# BB-ADC.net
KiCad netlist of a schematic drawn in Altium Designer
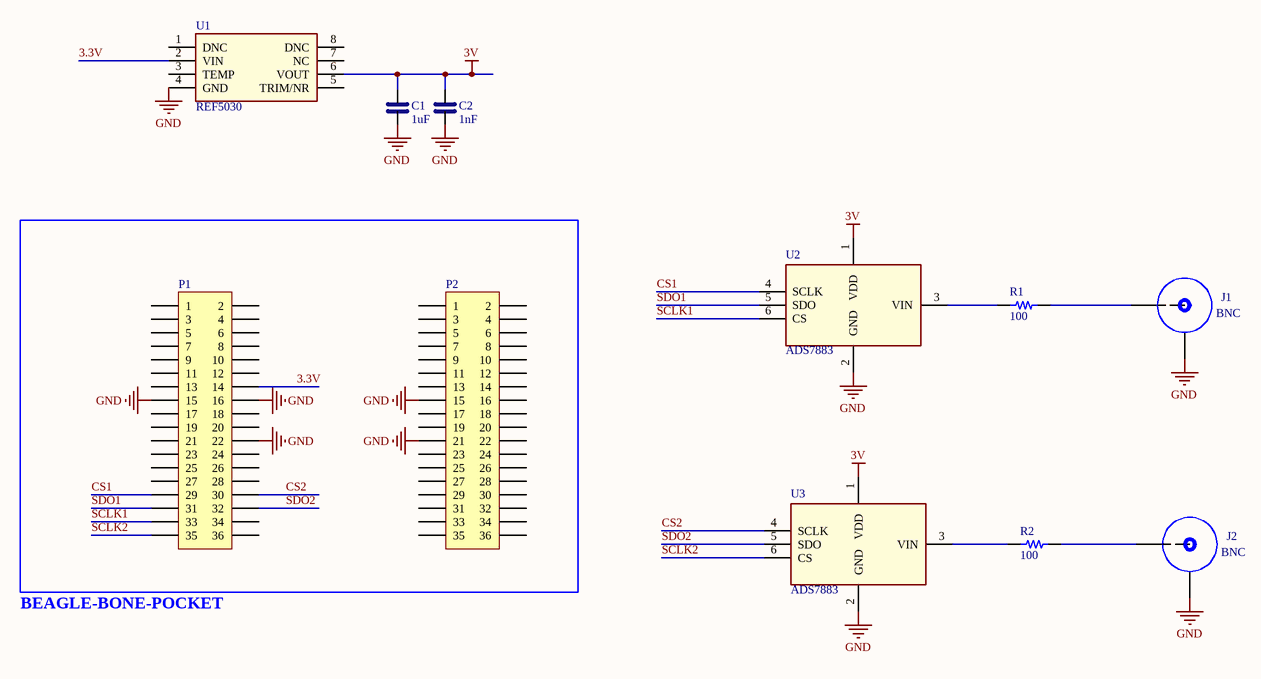
[diagram p0: BB-ADC.SchDoc]

(export (version "E")
  (design (tool "Eeschema 10.0.6"))
  (components
    (comp (ref "C1")
      (value "1uF")
      (footprint "CAP 0805/2012")
      (libsource (lib "Capacitors") (part "CAP 0805/2012"))
    )
    (comp (ref "C2")
      (value "1nF")
      (footprint "CAP 0805/2012")
      (libsource (lib "Capacitors") (part "CAP 0805/2012"))
    )
    (comp (ref "J1")
      (value "BNC")
      (footprint "BNC Straight")
      (description "RF Connectors / Coaxial Connectors BNC")
      (libsource (lib "Connectors") (part "BNC"))
    )
    (comp (ref "J2")
      (value "BNC")
      (footprint "BNC Straight")
      (description "RF Connectors / Coaxial Connectors BNC")
      (libsource (lib "Connectors") (part "BNC"))
    )
    (comp (ref "P1")
      (value "Beagle-Pocket")
      (footprint "HDR2X18")
      (description "Header, 18-Pin, Dual row")
      (fields (field (name "PUBLISHER") "Altium Limited"))
      (libsource (lib "Miscellaneous Connectors") (part "Header 18X2"))
    )
    (comp (ref "P2")
      (value "Beagle-Pocket")
      (footprint "HDR2X18")
      (description "Header, 18-Pin, Dual row")
      (fields (field (name "PUBLISHER") "Altium Limited"))
      (libsource (lib "Miscellaneous Connectors") (part "Header 18X2"))
    )
    (comp (ref "R1")
      (value "100")
      (footprint "RES 0805/2012")
      (libsource (lib "Resistors") (part "RES 0805/2012 ( 1/8W )"))
    )
    (comp (ref "R2")
      (value "100")
      (footprint "RES 0805/2012")
      (libsource (lib "Resistors") (part "RES 0805/2012 ( 1/8W )"))
    )
    (comp (ref "U1")
      (value "REF5030")
      (footprint "SOIC-8 (150mil-3.9mm width)")
      (description "Series Voltage Reference IC ±0.1% 10mA")
      (libsource (lib "Integrated Circuits") (part "REF5030"))
    )
    (comp (ref "U2")
      (value "ADS7883")
      (footprint "SOT-23-6")
      (description "12 Bit Analog to Digital Converter 1 Input 1 SAR SOT-23-6")
      (libsource (lib "Integrated Circuits") (part "ADS7883"))
    )
    (comp (ref "U3")
      (value "ADS7883")
      (footprint "SOT-23-6")
      (description "12 Bit Analog to Digital Converter 1 Input 1 SAR SOT-23-6")
      (libsource (lib "Integrated Circuits") (part "ADS7883"))
    )
  )
  (nets
    (net (code "1") (name "/3.3V") (class "Default")
      (node (ref "P1") (pin "14") (pinfunction "14_14") (pintype "passive"))
      (node (ref "U1") (pin "2") (pinfunction "VIN_2") (pintype "passive"))
    )
    (net (code "2") (name "/CS1") (class "Default")
      (node (ref "P1") (pin "29") (pinfunction "29_29") (pintype "passive"))
      (node (ref "U2") (pin "4") (pinfunction "SCLK_4") (pintype "passive"))
    )
    (net (code "3") (name "/CS2") (class "Default")
      (node (ref "P1") (pin "30") (pinfunction "30_30") (pintype "passive"))
      (node (ref "U3") (pin "4") (pinfunction "SCLK_4") (pintype "passive"))
    )
    (net (code "4") (name "/SCLK1") (class "Default")
      (node (ref "P1") (pin "33") (pinfunction "33_33") (pintype "passive"))
      (node (ref "U2") (pin "6") (pinfunction "CS_6") (pintype "passive"))
    )
    (net (code "5") (name "/SCLK2") (class "Default")
      (node (ref "P1") (pin "35") (pinfunction "35_35") (pintype "passive"))
      (node (ref "U3") (pin "6") (pinfunction "CS_6") (pintype "passive"))
    )
    (net (code "6") (name "/SDO1") (class "Default")
      (node (ref "P1") (pin "31") (pinfunction "31_31") (pintype "passive"))
      (node (ref "U2") (pin "5") (pinfunction "SDO_5") (pintype "passive"))
    )
    (net (code "7") (name "/SDO2") (class "Default")
      (node (ref "P1") (pin "32") (pinfunction "32_32") (pintype "passive"))
      (node (ref "U3") (pin "5") (pinfunction "SDO_5") (pintype "passive"))
    )
    (net (code "8") (name "3V") (class "Default")
      (node (ref "C1") (pin "2") (pinfunction "2_2") (pintype "passive"))
      (node (ref "C2") (pin "2") (pinfunction "2_2") (pintype "passive"))
      (node (ref "U1") (pin "6") (pinfunction "VOUT_6") (pintype "passive"))
      (node (ref "U2") (pin "1") (pinfunction "VDD_1") (pintype "passive"))
      (node (ref "U3") (pin "1") (pinfunction "VDD_1") (pintype "passive"))
    )
    (net (code "9") (name "GND") (class "Default")
      (node (ref "C1") (pin "1") (pinfunction "1_1") (pintype "passive"))
      (node (ref "C2") (pin "1") (pinfunction "1_1") (pintype "passive"))
      (node (ref "J1") (pin "2") (pinfunction "2_2") (pintype "passive"))
      (node (ref "J2") (pin "2") (pinfunction "2_2") (pintype "passive"))
      (node (ref "P1") (pin "15") (pinfunction "15_15") (pintype "passive"))
      (node (ref "P1") (pin "16") (pinfunction "16_16") (pintype "passive"))
      (node (ref "P1") (pin "22") (pinfunction "22_22") (pintype "passive"))
      (node (ref "P2") (pin "15") (pinfunction "15_15") (pintype "passive"))
      (node (ref "P2") (pin "21") (pinfunction "21_21") (pintype "passive"))
      (node (ref "U1") (pin "4") (pinfunction "GND_4") (pintype "passive"))
      (node (ref "U2") (pin "2") (pinfunction "GND_2") (pintype "passive"))
      (node (ref "U3") (pin "2") (pinfunction "GND_2") (pintype "passive"))
    )
    (net (code "10") (name "Net-(J1-Pad1)") (class "Default")
      (node (ref "J1") (pin "1") (pinfunction "1_1") (pintype "passive"))
      (node (ref "R1") (pin "2") (pinfunction "2_2") (pintype "passive"))
    )
    (net (code "11") (name "Net-(J2-Pad1)") (class "Default")
      (node (ref "J2") (pin "1") (pinfunction "1_1") (pintype "passive"))
      (node (ref "R2") (pin "2") (pinfunction "2_2") (pintype "passive"))
    )
    (net (code "12") (name "Net-(U2-VIN)") (class "Default")
      (node (ref "R1") (pin "1") (pinfunction "1_1") (pintype "passive"))
      (node (ref "U2") (pin "3") (pinfunction "VIN_3") (pintype "passive"))
    )
    (net (code "13") (name "Net-(U3-VIN)") (class "Default")
      (node (ref "R2") (pin "1") (pinfunction "1_1") (pintype "passive"))
      (node (ref "U3") (pin "3") (pinfunction "VIN_3") (pintype "passive"))
    )
    (net (code "14") (name "unconnected-(P1-Pad1)") (class "Default")
      (node (ref "P1") (pin "1") (pinfunction "1_1") (pintype "passive"))
    )
    (net (code "15") (name "unconnected-(P1-Pad2)") (class "Default")
      (node (ref "P1") (pin "2") (pinfunction "2_2") (pintype "passive"))
    )
    (net (code "16") (name "unconnected-(P1-Pad3)") (class "Default")
      (node (ref "P1") (pin "3") (pinfunction "3_3") (pintype "passive"))
    )
    (net (code "17") (name "unconnected-(P1-Pad4)") (class "Default")
      (node (ref "P1") (pin "4") (pinfunction "4_4") (pintype "passive"))
    )
    (net (code "18") (name "unconnected-(P1-Pad5)") (class "Default")
      (node (ref "P1") (pin "5") (pinfunction "5_5") (pintype "passive"))
    )
    (net (code "19") (name "unconnected-(P1-Pad6)") (class "Default")
      (node (ref "P1") (pin "6") (pinfunction "6_6") (pintype "passive"))
    )
    (net (code "20") (name "unconnected-(P1-Pad7)") (class "Default")
      (node (ref "P1") (pin "7") (pinfunction "7_7") (pintype "passive"))
    )
    (net (code "21") (name "unconnected-(P1-Pad8)") (class "Default")
      (node (ref "P1") (pin "8") (pinfunction "8_8") (pintype "passive"))
    )
    (net (code "22") (name "unconnected-(P1-Pad9)") (class "Default")
      (node (ref "P1") (pin "9") (pinfunction "9_9") (pintype "passive"))
    )
    (net (code "23") (name "unconnected-(P1-Pad10)") (class "Default")
      (node (ref "P1") (pin "10") (pinfunction "10_10") (pintype "passive"))
    )
    (net (code "24") (name "unconnected-(P1-Pad11)") (class "Default")
      (node (ref "P1") (pin "11") (pinfunction "11_11") (pintype "passive"))
    )
    (net (code "25") (name "unconnected-(P1-Pad12)") (class "Default")
      (node (ref "P1") (pin "12") (pinfunction "12_12") (pintype "passive"))
    )
    (net (code "26") (name "unconnected-(P1-Pad13)") (class "Default")
      (node (ref "P1") (pin "13") (pinfunction "13_13") (pintype "passive"))
    )
    (net (code "27") (name "unconnected-(P1-Pad17)") (class "Default")
      (node (ref "P1") (pin "17") (pinfunction "17_17") (pintype "passive"))
    )
    (net (code "28") (name "unconnected-(P1-Pad18)") (class "Default")
      (node (ref "P1") (pin "18") (pinfunction "18_18") (pintype "passive"))
    )
    (net (code "29") (name "unconnected-(P1-Pad19)") (class "Default")
      (node (ref "P1") (pin "19") (pinfunction "19_19") (pintype "passive"))
    )
    (net (code "30") (name "unconnected-(P1-Pad20)") (class "Default")
      (node (ref "P1") (pin "20") (pinfunction "20_20") (pintype "passive"))
    )
    (net (code "31") (name "unconnected-(P1-Pad21)") (class "Default")
      (node (ref "P1") (pin "21") (pinfunction "21_21") (pintype "passive"))
    )
    (net (code "32") (name "unconnected-(P1-Pad23)") (class "Default")
      (node (ref "P1") (pin "23") (pinfunction "23_23") (pintype "passive"))
    )
    (net (code "33") (name "unconnected-(P1-Pad24)") (class "Default")
      (node (ref "P1") (pin "24") (pinfunction "24_24") (pintype "passive"))
    )
    (net (code "34") (name "unconnected-(P1-Pad25)") (class "Default")
      (node (ref "P1") (pin "25") (pinfunction "25_25") (pintype "passive"))
    )
    (net (code "35") (name "unconnected-(P1-Pad26)") (class "Default")
      (node (ref "P1") (pin "26") (pinfunction "26_26") (pintype "passive"))
    )
    (net (code "36") (name "unconnected-(P1-Pad27)") (class "Default")
      (node (ref "P1") (pin "27") (pinfunction "27_27") (pintype "passive"))
    )
    (net (code "37") (name "unconnected-(P1-Pad28)") (class "Default")
      (node (ref "P1") (pin "28") (pinfunction "28_28") (pintype "passive"))
    )
    (net (code "38") (name "unconnected-(P1-Pad34)") (class "Default")
      (node (ref "P1") (pin "34") (pinfunction "34_34") (pintype "passive"))
    )
    (net (code "39") (name "unconnected-(P1-Pad36)") (class "Default")
      (node (ref "P1") (pin "36") (pinfunction "36_36") (pintype "passive"))
    )
    (net (code "40") (name "unconnected-(P2-Pad1)") (class "Default")
      (node (ref "P2") (pin "1") (pinfunction "1_1") (pintype "passive"))
    )
    (net (code "41") (name "unconnected-(P2-Pad2)") (class "Default")
      (node (ref "P2") (pin "2") (pinfunction "2_2") (pintype "passive"))
    )
    (net (code "42") (name "unconnected-(P2-Pad3)") (class "Default")
      (node (ref "P2") (pin "3") (pinfunction "3_3") (pintype "passive"))
    )
    (net (code "43") (name "unconnected-(P2-Pad4)") (class "Default")
      (node (ref "P2") (pin "4") (pinfunction "4_4") (pintype "passive"))
    )
    (net (code "44") (name "unconnected-(P2-Pad5)") (class "Default")
      (node (ref "P2") (pin "5") (pinfunction "5_5") (pintype "passive"))
    )
    (net (code "45") (name "unconnected-(P2-Pad6)") (class "Default")
      (node (ref "P2") (pin "6") (pinfunction "6_6") (pintype "passive"))
    )
    (net (code "46") (name "unconnected-(P2-Pad7)") (class "Default")
      (node (ref "P2") (pin "7") (pinfunction "7_7") (pintype "passive"))
    )
    (net (code "47") (name "unconnected-(P2-Pad8)") (class "Default")
      (node (ref "P2") (pin "8") (pinfunction "8_8") (pintype "passive"))
    )
    (net (code "48") (name "unconnected-(P2-Pad9)") (class "Default")
      (node (ref "P2") (pin "9") (pinfunction "9_9") (pintype "passive"))
    )
    (net (code "49") (name "unconnected-(P2-Pad10)") (class "Default")
      (node (ref "P2") (pin "10") (pinfunction "10_10") (pintype "passive"))
    )
    (net (code "50") (name "unconnected-(P2-Pad11)") (class "Default")
      (node (ref "P2") (pin "11") (pinfunction "11_11") (pintype "passive"))
    )
    (net (code "51") (name "unconnected-(P2-Pad12)") (class "Default")
      (node (ref "P2") (pin "12") (pinfunction "12_12") (pintype "passive"))
    )
    (net (code "52") (name "unconnected-(P2-Pad13)") (class "Default")
      (node (ref "P2") (pin "13") (pinfunction "13_13") (pintype "passive"))
    )
    (net (code "53") (name "unconnected-(P2-Pad14)") (class "Default")
      (node (ref "P2") (pin "14") (pinfunction "14_14") (pintype "passive"))
    )
    (net (code "54") (name "unconnected-(P2-Pad16)") (class "Default")
      (node (ref "P2") (pin "16") (pinfunction "16_16") (pintype "passive"))
    )
    (net (code "55") (name "unconnected-(P2-Pad17)") (class "Default")
      (node (ref "P2") (pin "17") (pinfunction "17_17") (pintype "passive"))
    )
    (net (code "56") (name "unconnected-(P2-Pad18)") (class "Default")
      (node (ref "P2") (pin "18") (pinfunction "18_18") (pintype "passive"))
    )
    (net (code "57") (name "unconnected-(P2-Pad19)") (class "Default")
      (node (ref "P2") (pin "19") (pinfunction "19_19") (pintype "passive"))
    )
    (net (code "58") (name "unconnected-(P2-Pad20)") (class "Default")
      (node (ref "P2") (pin "20") (pinfunction "20_20") (pintype "passive"))
    )
    (net (code "59") (name "unconnected-(P2-Pad22)") (class "Default")
      (node (ref "P2") (pin "22") (pinfunction "22_22") (pintype "passive"))
    )
    (net (code "60") (name "unconnected-(P2-Pad23)") (class "Default")
      (node (ref "P2") (pin "23") (pinfunction "23_23") (pintype "passive"))
    )
    (net (code "61") (name "unconnected-(P2-Pad24)") (class "Default")
      (node (ref "P2") (pin "24") (pinfunction "24_24") (pintype "passive"))
    )
    (net (code "62") (name "unconnected-(P2-Pad25)") (class "Default")
      (node (ref "P2") (pin "25") (pinfunction "25_25") (pintype "passive"))
    )
    (net (code "63") (name "unconnected-(P2-Pad26)") (class "Default")
      (node (ref "P2") (pin "26") (pinfunction "26_26") (pintype "passive"))
    )
    (net (code "64") (name "unconnected-(P2-Pad27)") (class "Default")
      (node (ref "P2") (pin "27") (pinfunction "27_27") (pintype "passive"))
    )
    (net (code "65") (name "unconnected-(P2-Pad28)") (class "Default")
      (node (ref "P2") (pin "28") (pinfunction "28_28") (pintype "passive"))
    )
    (net (code "66") (name "unconnected-(P2-Pad29)") (class "Default")
      (node (ref "P2") (pin "29") (pinfunction "29_29") (pintype "passive"))
    )
    (net (code "67") (name "unconnected-(P2-Pad30)") (class "Default")
      (node (ref "P2") (pin "30") (pinfunction "30_30") (pintype "passive"))
    )
    (net (code "68") (name "unconnected-(P2-Pad31)") (class "Default")
      (node (ref "P2") (pin "31") (pinfunction "31_31") (pintype "passive"))
    )
    (net (code "69") (name "unconnected-(P2-Pad32)") (class "Default")
      (node (ref "P2") (pin "32") (pinfunction "32_32") (pintype "passive"))
    )
    (net (code "70") (name "unconnected-(P2-Pad33)") (class "Default")
      (node (ref "P2") (pin "33") (pinfunction "33_33") (pintype "passive"))
    )
    (net (code "71") (name "unconnected-(P2-Pad34)") (class "Default")
      (node (ref "P2") (pin "34") (pinfunction "34_34") (pintype "passive"))
    )
    (net (code "72") (name "unconnected-(P2-Pad35)") (class "Default")
      (node (ref "P2") (pin "35") (pinfunction "35_35") (pintype "passive"))
    )
    (net (code "73") (name "unconnected-(P2-Pad36)") (class "Default")
      (node (ref "P2") (pin "36") (pinfunction "36_36") (pintype "passive"))
    )
    (net (code "74") (name "unconnected-(U1-DNC-Pad1)") (class "Default")
      (node (ref "U1") (pin "1") (pinfunction "DNC_1") (pintype "passive"))
    )
    (net (code "75") (name "unconnected-(U1-DNC-Pad8)") (class "Default")
      (node (ref "U1") (pin "8") (pinfunction "DNC_8") (pintype "passive"))
    )
    (net (code "76") (name "unconnected-(U1-NC-Pad7)") (class "Default")
      (node (ref "U1") (pin "7") (pinfunction "NC_7") (pintype "passive"))
    )
    (net (code "77") (name "unconnected-(U1-TEMP-Pad3)") (class "Default")
      (node (ref "U1") (pin "3") (pinfunction "TEMP_3") (pintype "passive"))
    )
    (net (code "78") (name "unconnected-(U1-TRIM{slash}NR-Pad5)") (class "Default")
      (node (ref "U1") (pin "5") (pinfunction "TRIM/NR_5") (pintype "passive"))
    )
  )
)
